# DIGITAL_OUTPUT.net
KiCad netlist of a schematic drawn in Altium Designer
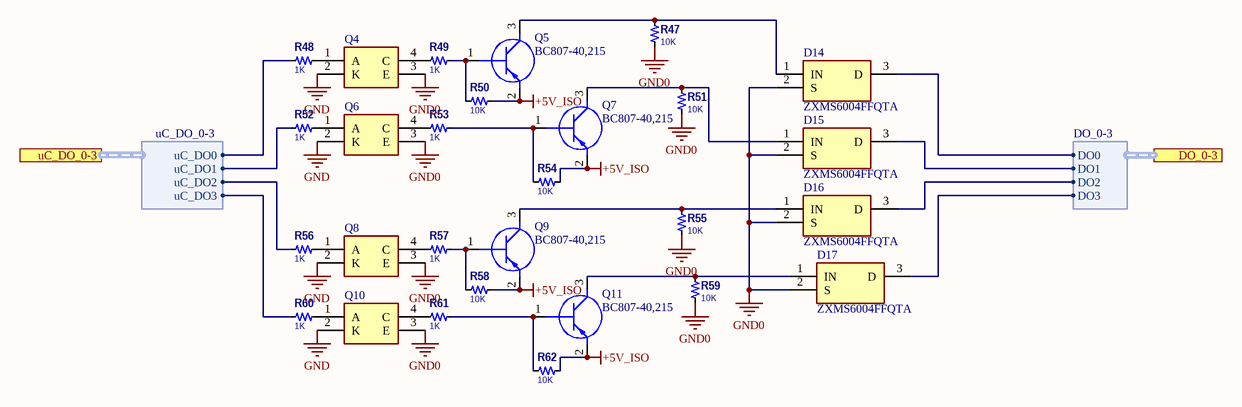
[diagram p0: DIGITAL_OUTPUT.SchDoc]

(export (version "E")
  (design (tool "Eeschema 10.0.6"))
  (components
    (comp (ref "D14")
      (value "ZXMS6004FFQTA")
      (footprint "SamacSys:SOTFL95P240X100-3N")
      (description "Diode")
      (fields (field (name "MOUSER PART NUMBER") "621-ZXMS6004FFQTA"))
      (libsource (lib "*") (part "ZXMS6004FFQTA"))
    )
    (comp (ref "D15")
      (value "ZXMS6004FFQTA")
      (footprint "SamacSys:SOTFL95P240X100-3N")
      (description "Diode")
      (fields (field (name "MOUSER PART NUMBER") "621-ZXMS6004FFQTA"))
      (libsource (lib "*") (part "ZXMS6004FFQTA"))
    )
    (comp (ref "D16")
      (value "ZXMS6004FFQTA")
      (footprint "SamacSys:SOTFL95P240X100-3N")
      (description "Diode")
      (fields (field (name "MOUSER PART NUMBER") "621-ZXMS6004FFQTA"))
      (libsource (lib "*") (part "ZXMS6004FFQTA"))
    )
    (comp (ref "D17")
      (value "ZXMS6004FFQTA")
      (footprint "SamacSys:SOTFL95P240X100-3N")
      (description "Diode")
      (fields (field (name "MOUSER PART NUMBER") "621-ZXMS6004FFQTA"))
      (libsource (lib "*") (part "ZXMS6004FFQTA"))
    )
    (comp (ref "Q4")
      (value "TLX9291A_GBTPL,F")
      (footprint "SamacSys:SOIC127P700X230-4N")
      (description "Phototransistor")
      (fields
        (field (name "MANUFACTURER_PART_NUMBER") "TLX9291A(GBTPL,F")
        (field (name "MOUSER PART NUMBER") "757-TLX9291AGBTPLF")
      )
      (libsource (lib "*") (part "TLX9291A_GBTPL,F"))
    )
    (comp (ref "Q5")
      (value "BC807-40,215")
      (footprint "SamacSys:SOT95P230X110-3N")
      (description "Transistor BJT PNP")
      (fields (field (name "MOUSER PART NUMBER") "771-BC807-40-T/R"))
      (libsource (lib "*") (part "BC807-40,215"))
    )
    (comp (ref "Q6")
      (value "TLX9291A_GBTPL,F")
      (footprint "SamacSys:SOIC127P700X230-4N")
      (description "Phototransistor")
      (fields
        (field (name "MANUFACTURER_PART_NUMBER") "TLX9291A(GBTPL,F")
        (field (name "MOUSER PART NUMBER") "757-TLX9291AGBTPLF")
      )
      (libsource (lib "*") (part "TLX9291A_GBTPL,F"))
    )
    (comp (ref "Q7")
      (value "BC807-40,215")
      (footprint "SamacSys:SOT95P230X110-3N")
      (description "Transistor BJT PNP")
      (fields (field (name "MOUSER PART NUMBER") "771-BC807-40-T/R"))
      (libsource (lib "*") (part "BC807-40,215"))
    )
    (comp (ref "Q8")
      (value "TLX9291A_GBTPL,F")
      (footprint "SamacSys:SOIC127P700X230-4N")
      (description "Phototransistor")
      (fields
        (field (name "MANUFACTURER_PART_NUMBER") "TLX9291A(GBTPL,F")
        (field (name "MOUSER PART NUMBER") "757-TLX9291AGBTPLF")
      )
      (libsource (lib "*") (part "TLX9291A_GBTPL,F"))
    )
    (comp (ref "Q9")
      (value "BC807-40,215")
      (footprint "SamacSys:SOT95P230X110-3N")
      (description "Transistor BJT PNP")
      (fields (field (name "MOUSER PART NUMBER") "771-BC807-40-T/R"))
      (libsource (lib "*") (part "BC807-40,215"))
    )
    (comp (ref "Q10")
      (value "TLX9291A_GBTPL,F")
      (footprint "SamacSys:SOIC127P700X230-4N")
      (description "Phototransistor")
      (fields
        (field (name "MANUFACTURER_PART_NUMBER") "TLX9291A(GBTPL,F")
        (field (name "MOUSER PART NUMBER") "757-TLX9291AGBTPLF")
      )
      (libsource (lib "*") (part "TLX9291A_GBTPL,F"))
    )
    (comp (ref "Q11")
      (value "BC807-40,215")
      (footprint "SamacSys:SOT95P230X110-3N")
      (description "Transistor BJT PNP")
      (fields (field (name "MOUSER PART NUMBER") "771-BC807-40-T/R"))
      (libsource (lib "*") (part "BC807-40,215"))
    )
    (comp (ref "R47")
      (value "10K")
      (footprint "0603-R")
      (fields
        (field (name "MANUFACTURER") "Panasonic")
        (field (name "MANUFACTURER PART NUMBER") "ERJ-8GEYJ621V")
        (field (name "TOLERANCE") "5%")
      )
      (libsource (lib "ESP32_IO_module") (part "Res_2"))
    )
    (comp (ref "R48")
      (value "1K")
      (footprint "0603-R")
      (fields
        (field (name "MANUFACTURER") "Panasonic")
        (field (name "MANUFACTURER PART NUMBER") "ERJ-8GEYJ621V")
        (field (name "TOLERANCE") "5%")
      )
      (libsource (lib "ESP32_IO_module") (part "Res_2"))
    )
    (comp (ref "R49")
      (value "1K")
      (footprint "0603-R")
      (fields
        (field (name "MANUFACTURER") "Panasonic")
        (field (name "MANUFACTURER PART NUMBER") "ERJ-8GEYJ621V")
        (field (name "TOLERANCE") "5%")
      )
      (libsource (lib "ESP32_IO_module") (part "Res_2"))
    )
    (comp (ref "R50")
      (value "10K")
      (footprint "0603-R")
      (fields
        (field (name "MANUFACTURER") "Panasonic")
        (field (name "MANUFACTURER PART NUMBER") "ERJ-8GEYJ621V")
        (field (name "TOLERANCE") "5%")
      )
      (libsource (lib "ESP32_IO_module") (part "Res_2"))
    )
    (comp (ref "R51")
      (value "10K")
      (footprint "0603-R")
      (fields
        (field (name "MANUFACTURER") "Panasonic")
        (field (name "MANUFACTURER PART NUMBER") "ERJ-8GEYJ621V")
        (field (name "TOLERANCE") "5%")
      )
      (libsource (lib "ESP32_IO_module") (part "Res_2"))
    )
    (comp (ref "R52")
      (value "1K")
      (footprint "0603-R")
      (fields
        (field (name "MANUFACTURER") "Panasonic")
        (field (name "MANUFACTURER PART NUMBER") "ERJ-8GEYJ621V")
        (field (name "TOLERANCE") "5%")
      )
      (libsource (lib "ESP32_IO_module") (part "Res_2"))
    )
    (comp (ref "R53")
      (value "1K")
      (footprint "0603-R")
      (fields
        (field (name "MANUFACTURER") "Panasonic")
        (field (name "MANUFACTURER PART NUMBER") "ERJ-8GEYJ621V")
        (field (name "TOLERANCE") "5%")
      )
      (libsource (lib "ESP32_IO_module") (part "Res_2"))
    )
    (comp (ref "R54")
      (value "10K")
      (footprint "0603-R")
      (fields
        (field (name "MANUFACTURER") "Panasonic")
        (field (name "MANUFACTURER PART NUMBER") "ERJ-8GEYJ621V")
        (field (name "TOLERANCE") "5%")
      )
      (libsource (lib "ESP32_IO_module") (part "Res_2"))
    )
    (comp (ref "R55")
      (value "10K")
      (footprint "0603-R")
      (fields
        (field (name "MANUFACTURER") "Panasonic")
        (field (name "MANUFACTURER PART NUMBER") "ERJ-8GEYJ621V")
        (field (name "TOLERANCE") "5%")
      )
      (libsource (lib "ESP32_IO_module") (part "Res_2"))
    )
    (comp (ref "R56")
      (value "1K")
      (footprint "0603-R")
      (fields
        (field (name "MANUFACTURER") "Panasonic")
        (field (name "MANUFACTURER PART NUMBER") "ERJ-8GEYJ621V")
        (field (name "TOLERANCE") "5%")
      )
      (libsource (lib "ESP32_IO_module") (part "Res_2"))
    )
    (comp (ref "R57")
      (value "1K")
      (footprint "0603-R")
      (fields
        (field (name "MANUFACTURER") "Panasonic")
        (field (name "MANUFACTURER PART NUMBER") "ERJ-8GEYJ621V")
        (field (name "TOLERANCE") "5%")
      )
      (libsource (lib "ESP32_IO_module") (part "Res_2"))
    )
    (comp (ref "R58")
      (value "10K")
      (footprint "0603-R")
      (fields
        (field (name "MANUFACTURER") "Panasonic")
        (field (name "MANUFACTURER PART NUMBER") "ERJ-8GEYJ621V")
        (field (name "TOLERANCE") "5%")
      )
      (libsource (lib "ESP32_IO_module") (part "Res_2"))
    )
    (comp (ref "R59")
      (value "10K")
      (footprint "0603-R")
      (fields
        (field (name "MANUFACTURER") "Panasonic")
        (field (name "MANUFACTURER PART NUMBER") "ERJ-8GEYJ621V")
        (field (name "TOLERANCE") "5%")
      )
      (libsource (lib "ESP32_IO_module") (part "Res_2"))
    )
    (comp (ref "R60")
      (value "1K")
      (footprint "0603-R")
      (fields
        (field (name "MANUFACTURER") "Panasonic")
        (field (name "MANUFACTURER PART NUMBER") "ERJ-8GEYJ621V")
        (field (name "TOLERANCE") "5%")
      )
      (libsource (lib "ESP32_IO_module") (part "Res_2"))
    )
    (comp (ref "R61")
      (value "1K")
      (footprint "0603-R")
      (fields
        (field (name "MANUFACTURER") "Panasonic")
        (field (name "MANUFACTURER PART NUMBER") "ERJ-8GEYJ621V")
        (field (name "TOLERANCE") "5%")
      )
      (libsource (lib "ESP32_IO_module") (part "Res_2"))
    )
    (comp (ref "R62")
      (value "10K")
      (footprint "0603-R")
      (fields
        (field (name "MANUFACTURER") "Panasonic")
        (field (name "MANUFACTURER PART NUMBER") "ERJ-8GEYJ621V")
        (field (name "TOLERANCE") "5%")
      )
      (libsource (lib "ESP32_IO_module") (part "Res_2"))
    )
  )
  (nets
    (net (code "3") (name "+5V_ISO") (class "Default")
      (node (ref "Q11") (pin "2") (pinfunction "E_2") (pintype "passive"))
      (node (ref "Q5") (pin "2") (pinfunction "E_2") (pintype "passive"))
      (node (ref "Q7") (pin "2") (pinfunction "E_2") (pintype "passive"))
      (node (ref "Q9") (pin "2") (pinfunction "E_2") (pintype "passive"))
      (node (ref "R50") (pin "2") (pinfunction "2_2") (pintype "passive"))
      (node (ref "R54") (pin "2") (pinfunction "2_2") (pintype "passive"))
      (node (ref "R58") (pin "2") (pinfunction "2_2") (pintype "passive"))
      (node (ref "R62") (pin "2") (pinfunction "2_2") (pintype "passive"))
    )
    (net (code "4") (name "/DO0") (class "Default")
      (node (ref "D14") (pin "3") (pinfunction "D_3") (pintype "passive"))
    )
    (net (code "5") (name "/DO1") (class "Default")
      (node (ref "D15") (pin "3") (pinfunction "D_3") (pintype "passive"))
    )
    (net (code "6") (name "/DO2") (class "Default")
      (node (ref "D16") (pin "3") (pinfunction "D_3") (pintype "passive"))
    )
    (net (code "7") (name "/DO3") (class "Default")
      (node (ref "D17") (pin "3") (pinfunction "D_3") (pintype "passive"))
    )
    (net (code "8") (name "/uC_DO0") (class "Default")
      (node (ref "R48") (pin "1") (pinfunction "1_1") (pintype "passive"))
    )
    (net (code "9") (name "/uC_DO1") (class "Default")
      (node (ref "R52") (pin "1") (pinfunction "1_1") (pintype "passive"))
    )
    (net (code "10") (name "/uC_DO2") (class "Default")
      (node (ref "R56") (pin "1") (pinfunction "1_1") (pintype "passive"))
    )
    (net (code "11") (name "/uC_DO3") (class "Default")
      (node (ref "R60") (pin "1") (pinfunction "1_1") (pintype "passive"))
    )
    (net (code "14") (name "GND") (class "Default")
      (node (ref "Q10") (pin "2") (pinfunction "K_2") (pintype "passive"))
      (node (ref "Q4") (pin "2") (pinfunction "K_2") (pintype "passive"))
      (node (ref "Q6") (pin "2") (pinfunction "K_2") (pintype "passive"))
      (node (ref "Q8") (pin "2") (pinfunction "K_2") (pintype "passive"))
    )
    (net (code "15") (name "GND0") (class "Default")
      (node (ref "D14") (pin "2") (pinfunction "S_2") (pintype "passive"))
      (node (ref "D15") (pin "2") (pinfunction "S_2") (pintype "passive"))
      (node (ref "D16") (pin "2") (pinfunction "S_2") (pintype "passive"))
      (node (ref "D17") (pin "2") (pinfunction "S_2") (pintype "passive"))
      (node (ref "Q10") (pin "3") (pinfunction "E_3") (pintype "passive"))
      (node (ref "Q4") (pin "3") (pinfunction "E_3") (pintype "passive"))
      (node (ref "Q6") (pin "3") (pinfunction "E_3") (pintype "passive"))
      (node (ref "Q8") (pin "3") (pinfunction "E_3") (pintype "passive"))
      (node (ref "R47") (pin "1") (pinfunction "1_1") (pintype "passive"))
      (node (ref "R51") (pin "1") (pinfunction "1_1") (pintype "passive"))
      (node (ref "R55") (pin "1") (pinfunction "1_1") (pintype "passive"))
      (node (ref "R59") (pin "1") (pinfunction "1_1") (pintype "passive"))
    )
    (net (code "16") (name "Net-(D14-IN)") (class "Default")
      (node (ref "D14") (pin "1") (pinfunction "IN_1") (pintype "passive"))
      (node (ref "Q5") (pin "3") (pinfunction "C_3") (pintype "passive"))
      (node (ref "R47") (pin "2") (pinfunction "2_2") (pintype "passive"))
    )
    (net (code "17") (name "Net-(D15-IN)") (class "Default")
      (node (ref "D15") (pin "1") (pinfunction "IN_1") (pintype "passive"))
      (node (ref "Q7") (pin "3") (pinfunction "C_3") (pintype "passive"))
      (node (ref "R51") (pin "2") (pinfunction "2_2") (pintype "passive"))
    )
    (net (code "18") (name "Net-(D16-IN)") (class "Default")
      (node (ref "D16") (pin "1") (pinfunction "IN_1") (pintype "passive"))
      (node (ref "Q9") (pin "3") (pinfunction "C_3") (pintype "passive"))
      (node (ref "R55") (pin "2") (pinfunction "2_2") (pintype "passive"))
    )
    (net (code "19") (name "Net-(D17-IN)") (class "Default")
      (node (ref "D17") (pin "1") (pinfunction "IN_1") (pintype "passive"))
      (node (ref "Q11") (pin "3") (pinfunction "C_3") (pintype "passive"))
      (node (ref "R59") (pin "2") (pinfunction "2_2") (pintype "passive"))
    )
    (net (code "20") (name "Net-(Q4-A)") (class "Default")
      (node (ref "Q4") (pin "1") (pinfunction "A_1") (pintype "passive"))
      (node (ref "R48") (pin "2") (pinfunction "2_2") (pintype "passive"))
    )
    (net (code "21") (name "Net-(Q4-C)") (class "Default")
      (node (ref "Q4") (pin "4") (pinfunction "C_4") (pintype "passive"))
      (node (ref "R49") (pin "1") (pinfunction "1_1") (pintype "passive"))
    )
    (net (code "22") (name "Net-(Q5-B)") (class "Default")
      (node (ref "Q5") (pin "1") (pinfunction "B_1") (pintype "passive"))
      (node (ref "R49") (pin "2") (pinfunction "2_2") (pintype "passive"))
      (node (ref "R50") (pin "1") (pinfunction "1_1") (pintype "passive"))
    )
    (net (code "23") (name "Net-(Q6-A)") (class "Default")
      (node (ref "Q6") (pin "1") (pinfunction "A_1") (pintype "passive"))
      (node (ref "R52") (pin "2") (pinfunction "2_2") (pintype "passive"))
    )
    (net (code "24") (name "Net-(Q6-C)") (class "Default")
      (node (ref "Q6") (pin "4") (pinfunction "C_4") (pintype "passive"))
      (node (ref "R53") (pin "1") (pinfunction "1_1") (pintype "passive"))
    )
    (net (code "25") (name "Net-(Q7-B)") (class "Default")
      (node (ref "Q7") (pin "1") (pinfunction "B_1") (pintype "passive"))
      (node (ref "R53") (pin "2") (pinfunction "2_2") (pintype "passive"))
      (node (ref "R54") (pin "1") (pinfunction "1_1") (pintype "passive"))
    )
    (net (code "26") (name "Net-(Q8-A)") (class "Default")
      (node (ref "Q8") (pin "1") (pinfunction "A_1") (pintype "passive"))
      (node (ref "R56") (pin "2") (pinfunction "2_2") (pintype "passive"))
    )
    (net (code "27") (name "Net-(Q8-C)") (class "Default")
      (node (ref "Q8") (pin "4") (pinfunction "C_4") (pintype "passive"))
      (node (ref "R57") (pin "1") (pinfunction "1_1") (pintype "passive"))
    )
    (net (code "28") (name "Net-(Q9-B)") (class "Default")
      (node (ref "Q9") (pin "1") (pinfunction "B_1") (pintype "passive"))
      (node (ref "R57") (pin "2") (pinfunction "2_2") (pintype "passive"))
      (node (ref "R58") (pin "1") (pinfunction "1_1") (pintype "passive"))
    )
    (net (code "29") (name "Net-(Q10-A)") (class "Default")
      (node (ref "Q10") (pin "1") (pinfunction "A_1") (pintype "passive"))
      (node (ref "R60") (pin "2") (pinfunction "2_2") (pintype "passive"))
    )
    (net (code "30") (name "Net-(Q10-C)") (class "Default")
      (node (ref "Q10") (pin "4") (pinfunction "C_4") (pintype "passive"))
      (node (ref "R61") (pin "1") (pinfunction "1_1") (pintype "passive"))
    )
    (net (code "31") (name "Net-(Q11-B)") (class "Default")
      (node (ref "Q11") (pin "1") (pinfunction "B_1") (pintype "passive"))
      (node (ref "R61") (pin "2") (pinfunction "2_2") (pintype "passive"))
      (node (ref "R62") (pin "1") (pinfunction "1_1") (pintype "passive"))
    )
  )
)
